# ICS40300-preamp-surfacemount_Rev-B.net
KiCad netlist of a schematic drawn in EAGLE
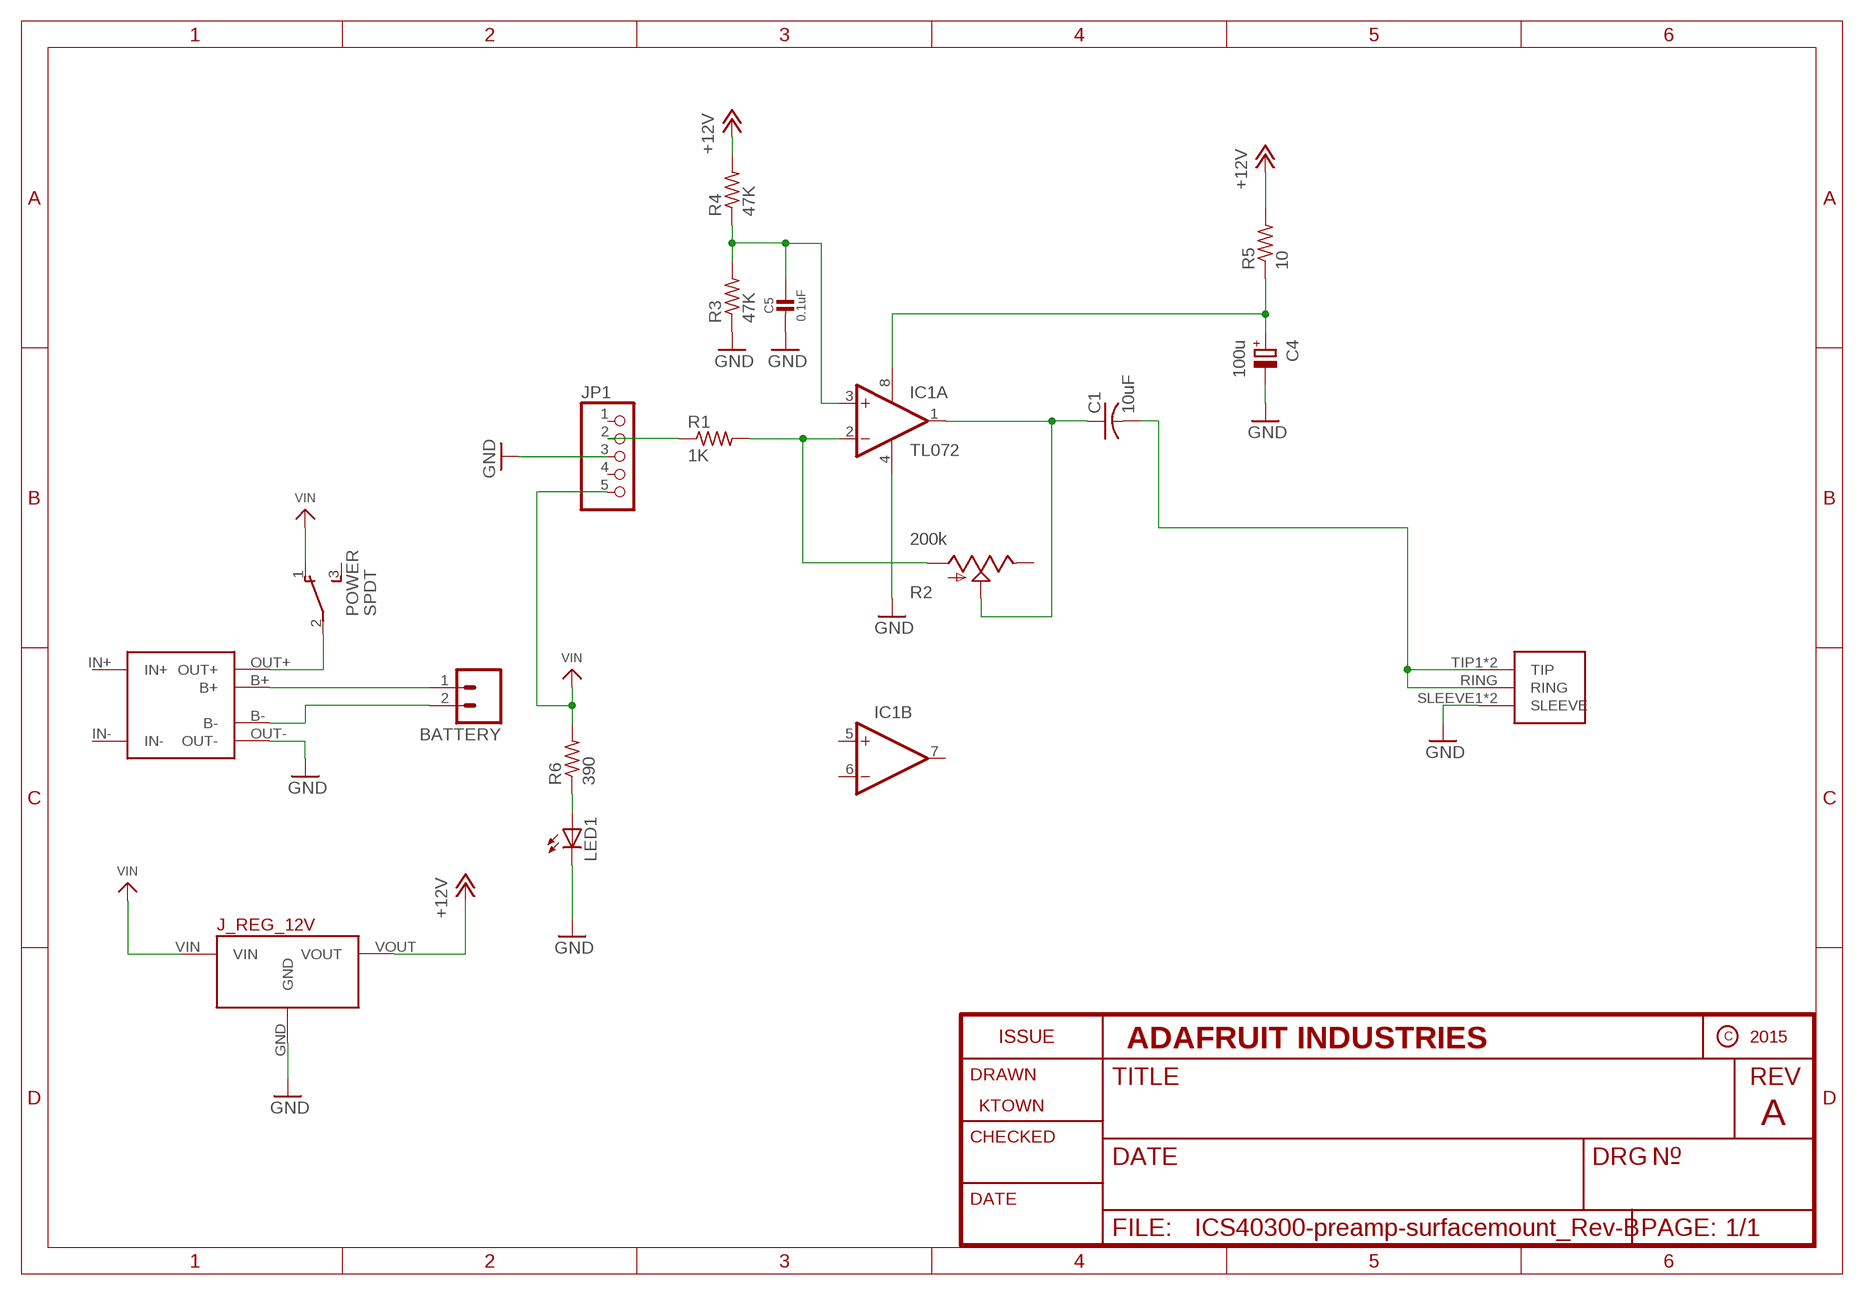
[diagram p0: schematic, sheet 1]

(export (version "E")
  (design (tool "Eeschema 10.0.6"))
  (components
    (comp (ref "BATTERY")
      (value "M02LOCK")
      (footprint "eagle-import:1X02_LOCK")
      (libsource (lib "eagle-import") (part "M02LOCK"))
    )
    (comp (ref "C1")
      (value "10uF")
      (footprint "eagle-import:C0805K")
      (libsource (lib "eagle-import") (part "C-USC0805K"))
    )
    (comp (ref "C4")
      (value "100u")
      (footprint "eagle-import:TT2D4L")
      (libsource (lib "eagle-import") (part "CPOL-EUTT2D4L"))
    )
    (comp (ref "C5")
      (value "0.1uF")
      (footprint "eagle-import:0805-NO")
      (libsource (lib "eagle-import") (part "CAP_CERAMIC0805-NOOUTLINE"))
    )
    (comp (ref "IC1")
      (value "TL072")
      (footprint "eagle-import:SO08")
      (fields (field (name "IC_NAME") "TL072"))
      (libsource (lib "eagle-import") (part "OPA2UA134"))
    )
    (comp (ref "JP1")
      (value "HEADER-1X576MIL")
      (footprint "eagle-import:1X05_ROUND_76")
      (libsource (lib "eagle-import") (part "HEADER-1X576MIL"))
    )
    (comp (ref "J_REG_12V")
      (value "POLOLU_VOLTAGE_REGULATORS_3PIN")
      (footprint "eagle-import:POLOLU_5V-12V_STEPUP_U3V12F5-U3V12F12")
      (libsource (lib "eagle-import") (part "POLOLU_VOLTAGE_REGULATORS_3PIN"))
    )
    (comp (ref "LED1")
      (value "LED3MM")
      (footprint "eagle-import:LED3MM")
      (libsource (lib "eagle-import") (part "LED3MM"))
    )
    (comp (ref "POWER")
      (value "SPDT")
      (footprint "eagle-import:SWITCH_SPDT-TE-CONNECT")
      (libsource (lib "eagle-import") (part "SWITCH_SPDTTE-CONNECT"))
    )
    (comp (ref "R1")
      (value "1K")
      (footprint "eagle-import:R0805")
      (libsource (lib "eagle-import") (part "R-US_R0805"))
    )
    (comp (ref "R2")
      (value "200k")
      (footprint "eagle-import:TRIMPOT-BOURNS-3306W")
      (libsource (lib "eagle-import") (part "TRIMPOT-BOURNS3306W"))
    )
    (comp (ref "R3")
      (value "47K")
      (footprint "eagle-import:R0805")
      (libsource (lib "eagle-import") (part "R-US_R0805"))
    )
    (comp (ref "R4")
      (value "47K")
      (footprint "eagle-import:R0805")
      (libsource (lib "eagle-import") (part "R-US_R0805"))
    )
    (comp (ref "R5")
      (value "10")
      (footprint "eagle-import:R0805")
      (libsource (lib "eagle-import") (part "R-US_R0805"))
    )
    (comp (ref "R6")
      (value "390")
      (footprint "eagle-import:R0805")
      (libsource (lib "eagle-import") (part "R-US_R0805"))
    )
    (comp (ref "U$1")
      (value "TP4056-MODULETP4056")
      (footprint "eagle-import:TP4056-LITHIUM-PROTECTED-MODULE-MOVED-PAD")
      (libsource (lib "eagle-import") (part "TP4056-MODULETP4056"))
    )
    (comp (ref "U$13")
      (value "1/8\"-F-STEREO-PCB")
      (footprint "eagle-import:1_8_-F-STEREO-PCB")
      (libsource (lib "eagle-import") (part "1/8{dblquote}-F-STEREO-PCB"))
    )
  )
  (nets
    (net (code "1") (name "+12V") (class "Default")
      (node (ref "J_REG_12V") (pin "VOUT") (pinfunction "VOUT_VOUT") (pintype "bidirectional"))
      (node (ref "R4") (pin "2") (pinfunction "2_2") (pintype "passive"))
      (node (ref "R5") (pin "2") (pinfunction "2_2") (pintype "passive"))
    )
    (net (code "2") (name "/IN+") (class "Default")
      (node (ref "U$1") (pin "IN+") (pinfunction "IN+_IN+") (pintype "power_in"))
    )
    (net (code "3") (name "/IN-") (class "Default")
      (node (ref "U$1") (pin "IN-") (pinfunction "IN-_IN-") (pintype "power_in"))
    )
    (net (code "4") (name "GND") (class "Default")
      (node (ref "C4") (pin "-") (pinfunction "-_-") (pintype "passive"))
      (node (ref "C5") (pin "2") (pinfunction "2_2") (pintype "passive"))
      (node (ref "IC1") (pin "4") (pinfunction "V-_4") (pintype "power_in"))
      (node (ref "JP1") (pin "3") (pinfunction "3_3") (pintype "passive"))
      (node (ref "J_REG_12V") (pin "GND") (pinfunction "GND_GND") (pintype "bidirectional"))
      (node (ref "LED1") (pin "K") (pinfunction "C_K") (pintype "passive"))
      (node (ref "R3") (pin "1") (pinfunction "1_1") (pintype "passive"))
      (node (ref "U$1") (pin "OUT-") (pinfunction "OUT-_OUT-") (pintype "power_in"))
      (node (ref "U$13") (pin "SLEEVE1") (pinfunction "SLEEVE_SLEEVE1") (pintype "bidirectional"))
      (node (ref "U$13") (pin "SLEEVE2") (pinfunction "SLEEVE_SLEEVE2") (pintype "bidirectional"))
    )
    (net (code "5") (name "Net-(BATTERY-Pad1)") (class "Default")
      (node (ref "BATTERY") (pin "1") (pinfunction "1_1") (pintype "passive"))
      (node (ref "U$1") (pin "B+") (pinfunction "B+_B+") (pintype "power_in"))
    )
    (net (code "6") (name "Net-(BATTERY-Pad2)") (class "Default")
      (node (ref "BATTERY") (pin "2") (pinfunction "2_2") (pintype "passive"))
      (node (ref "U$1") (pin "B-") (pinfunction "B-_B-") (pintype "power_in"))
    )
    (net (code "7") (name "Net-(C1-Pad2)") (class "Default")
      (node (ref "C1") (pin "2") (pinfunction "2_2") (pintype "passive"))
      (node (ref "U$13") (pin "RING") (pinfunction "RING_RING") (pintype "bidirectional"))
      (node (ref "U$13") (pin "TIP1") (pinfunction "TIP_TIP1") (pintype "bidirectional"))
      (node (ref "U$13") (pin "TIP2") (pinfunction "TIP_TIP2") (pintype "bidirectional"))
    )
    (net (code "8") (name "Net-(IC1A-+IN)") (class "Default")
      (node (ref "C5") (pin "1") (pinfunction "1_1") (pintype "passive"))
      (node (ref "IC1") (pin "3") (pinfunction "+IN_3") (pintype "input"))
      (node (ref "R3") (pin "2") (pinfunction "2_2") (pintype "passive"))
      (node (ref "R4") (pin "1") (pinfunction "1_1") (pintype "passive"))
    )
    (net (code "9") (name "Net-(IC1A--IN)") (class "Default")
      (node (ref "IC1") (pin "2") (pinfunction "-IN_2") (pintype "input"))
      (node (ref "R1") (pin "2") (pinfunction "2_2") (pintype "passive"))
      (node (ref "R2") (pin "P$1") (pinfunction "IN_P$1") (pintype "passive"))
    )
    (net (code "10") (name "Net-(IC1A-OUT)") (class "Default")
      (node (ref "C1") (pin "1") (pinfunction "1_1") (pintype "passive"))
      (node (ref "IC1") (pin "1") (pinfunction "OUT_1") (pintype "output"))
      (node (ref "R2") (pin "P$2") (pinfunction "WIPER_P$2") (pintype "passive"))
    )
    (net (code "11") (name "Net-(IC1A-V+)") (class "Default")
      (node (ref "C4") (pin "+") (pinfunction "+_+") (pintype "passive"))
      (node (ref "IC1") (pin "8") (pinfunction "V+_8") (pintype "power_in"))
      (node (ref "R5") (pin "1") (pinfunction "1_1") (pintype "passive"))
    )
    (net (code "12") (name "Net-(JP1-Pad2)") (class "Default")
      (node (ref "JP1") (pin "2") (pinfunction "2_2") (pintype "passive"))
      (node (ref "R1") (pin "1") (pinfunction "1_1") (pintype "passive"))
    )
    (net (code "13") (name "Net-(LED1-PadA)") (class "Default")
      (node (ref "LED1") (pin "A") (pinfunction "A_A") (pintype "passive"))
      (node (ref "R6") (pin "1") (pinfunction "1_1") (pintype "passive"))
    )
    (net (code "14") (name "Net-(POWER-Pad2)") (class "Default")
      (node (ref "POWER") (pin "2") (pinfunction "2_2") (pintype "passive"))
      (node (ref "U$1") (pin "OUT+") (pinfunction "OUT+_OUT+") (pintype "power_in"))
    )
    (net (code "15") (name "VIN") (class "Default")
      (node (ref "JP1") (pin "5") (pinfunction "5_5") (pintype "passive"))
      (node (ref "J_REG_12V") (pin "VIN") (pinfunction "VIN_VIN") (pintype "bidirectional"))
      (node (ref "POWER") (pin "1") (pinfunction "1_1") (pintype "passive"))
      (node (ref "R6") (pin "2") (pinfunction "2_2") (pintype "passive"))
    )
    (net (code "16") (name "unconnected-(IC1B-+IN-Pad5)") (class "Default")
      (node (ref "IC1") (pin "5") (pinfunction "+IN_5") (pintype "input"))
    )
    (net (code "17") (name "unconnected-(IC1B--IN-Pad6)") (class "Default")
      (node (ref "IC1") (pin "6") (pinfunction "-IN_6") (pintype "input"))
    )
    (net (code "18") (name "unconnected-(IC1B-OUT-Pad7)") (class "Default")
      (node (ref "IC1") (pin "7") (pinfunction "OUT_7") (pintype "output"))
    )
    (net (code "19") (name "unconnected-(JP1-Pad1)") (class "Default")
      (node (ref "JP1") (pin "1") (pinfunction "1_1") (pintype "passive"))
    )
    (net (code "20") (name "unconnected-(JP1-Pad4)") (class "Default")
      (node (ref "JP1") (pin "4") (pinfunction "4_4") (pintype "passive"))
    )
    (net (code "21") (name "unconnected-(POWER-Pad3)") (class "Default")
      (node (ref "POWER") (pin "3") (pinfunction "3_3") (pintype "passive"))
    )
    (net (code "22") (name "unconnected-(R2-OUT-PadP$3)") (class "Default")
      (node (ref "R2") (pin "P$3") (pinfunction "OUT_P$3") (pintype "passive"))
    )
  )
)
